# Sensors.net
KiCad netlist of a schematic drawn in Altium Designer
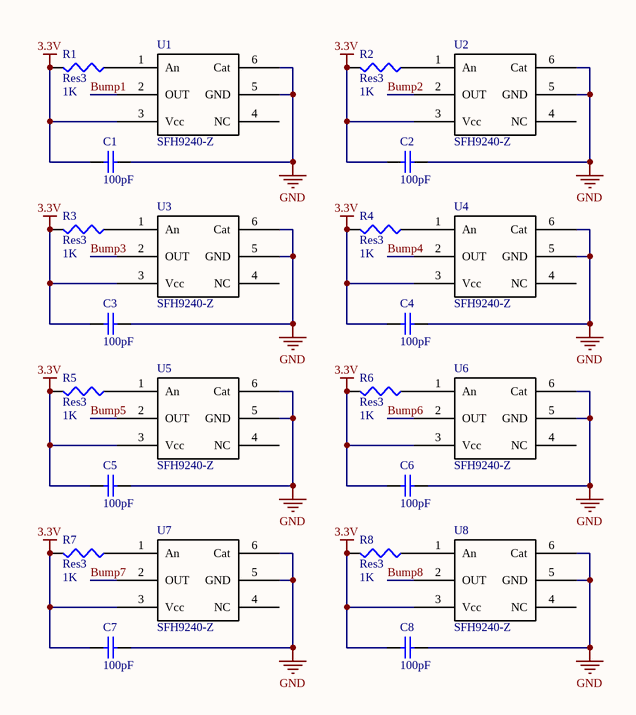
[diagram p0: Sensors.SchDoc]

(export (version "E")
  (design (tool "Eeschema 10.0.6"))
  (components
    (comp (ref "C1")
      (value "100pF")
      (footprint "CAPC1005L")
      (description "Capacitor (Semiconductor SIM Model)")
      (fields (field (name "Comment") "Cap Semi") (field (name "PUBLISHER") "Altium Limited"))
      (libsource (lib "Miscellaneous Devices") (part "Cap Semi"))
    )
    (comp (ref "C2")
      (value "100pF")
      (footprint "CAPC1005L")
      (description "Capacitor (Semiconductor SIM Model)")
      (fields (field (name "Comment") "Cap Semi") (field (name "PUBLISHER") "Altium Limited"))
      (libsource (lib "Miscellaneous Devices") (part "Cap Semi"))
    )
    (comp (ref "C3")
      (value "100pF")
      (footprint "CAPC1005L")
      (description "Capacitor (Semiconductor SIM Model)")
      (fields (field (name "Comment") "Cap Semi") (field (name "PUBLISHER") "Altium Limited"))
      (libsource (lib "Miscellaneous Devices") (part "Cap Semi"))
    )
    (comp (ref "C4")
      (value "100pF")
      (footprint "CAPC1005L")
      (description "Capacitor (Semiconductor SIM Model)")
      (fields (field (name "Comment") "Cap Semi") (field (name "PUBLISHER") "Altium Limited"))
      (libsource (lib "Miscellaneous Devices") (part "Cap Semi"))
    )
    (comp (ref "C5")
      (value "100pF")
      (footprint "CAPC1005L")
      (description "Capacitor (Semiconductor SIM Model)")
      (fields (field (name "Comment") "Cap Semi") (field (name "PUBLISHER") "Altium Limited"))
      (libsource (lib "Miscellaneous Devices") (part "Cap Semi"))
    )
    (comp (ref "C6")
      (value "100pF")
      (footprint "CAPC1005L")
      (description "Capacitor (Semiconductor SIM Model)")
      (fields (field (name "Comment") "Cap Semi") (field (name "PUBLISHER") "Altium Limited"))
      (libsource (lib "Miscellaneous Devices") (part "Cap Semi"))
    )
    (comp (ref "C7")
      (value "100pF")
      (footprint "CAPC1005L")
      (description "Capacitor (Semiconductor SIM Model)")
      (fields (field (name "Comment") "Cap Semi") (field (name "PUBLISHER") "Altium Limited"))
      (libsource (lib "Miscellaneous Devices") (part "Cap Semi"))
    )
    (comp (ref "C8")
      (value "100pF")
      (footprint "CAPC1005L")
      (description "Capacitor (Semiconductor SIM Model)")
      (fields (field (name "Comment") "Cap Semi") (field (name "PUBLISHER") "Altium Limited"))
      (libsource (lib "Miscellaneous Devices") (part "Cap Semi"))
    )
    (comp (ref "R1")
      (value "Res3")
      (footprint "RESC1608L")
      (description "Resistor")
      (fields (field (name "ALTIUM_VALUE") "1K") (field (name "PUBLISHER") "Altium Limited"))
      (libsource (lib "Miscellaneous Devices") (part "Res3"))
    )
    (comp (ref "R2")
      (value "Res3")
      (footprint "RESC1608L")
      (description "Resistor")
      (fields (field (name "ALTIUM_VALUE") "1K") (field (name "PUBLISHER") "Altium Limited"))
      (libsource (lib "Miscellaneous Devices") (part "Res3"))
    )
    (comp (ref "R3")
      (value "Res3")
      (footprint "RESC1608L")
      (description "Resistor")
      (fields (field (name "ALTIUM_VALUE") "1K") (field (name "PUBLISHER") "Altium Limited"))
      (libsource (lib "Miscellaneous Devices") (part "Res3"))
    )
    (comp (ref "R4")
      (value "Res3")
      (footprint "RESC1608L")
      (description "Resistor")
      (fields (field (name "ALTIUM_VALUE") "1K") (field (name "PUBLISHER") "Altium Limited"))
      (libsource (lib "Miscellaneous Devices") (part "Res3"))
    )
    (comp (ref "R5")
      (value "Res3")
      (footprint "RESC1608L")
      (description "Resistor")
      (fields (field (name "ALTIUM_VALUE") "1K") (field (name "PUBLISHER") "Altium Limited"))
      (libsource (lib "Miscellaneous Devices") (part "Res3"))
    )
    (comp (ref "R6")
      (value "Res3")
      (footprint "RESC1608L")
      (description "Resistor")
      (fields (field (name "ALTIUM_VALUE") "1K") (field (name "PUBLISHER") "Altium Limited"))
      (libsource (lib "Miscellaneous Devices") (part "Res3"))
    )
    (comp (ref "R7")
      (value "Res3")
      (footprint "RESC1608L")
      (description "Resistor")
      (fields (field (name "ALTIUM_VALUE") "1K") (field (name "PUBLISHER") "Altium Limited"))
      (libsource (lib "Miscellaneous Devices") (part "Res3"))
    )
    (comp (ref "R8")
      (value "Res3")
      (footprint "RESC1608L")
      (description "Resistor")
      (fields (field (name "ALTIUM_VALUE") "1K") (field (name "PUBLISHER") "Altium Limited"))
      (libsource (lib "Miscellaneous Devices") (part "Res3"))
    )
    (comp (ref "U1") (value "SFH9240-Z") (footprint "SFH9240-Z") (libsource (lib "mrone") (part "SFH9240-Z")))
    (comp (ref "U2") (value "SFH9240-Z") (footprint "SFH9240-Z") (libsource (lib "mrone") (part "SFH9240-Z")))
    (comp (ref "U3") (value "SFH9240-Z") (footprint "SFH9240-Z") (libsource (lib "mrone") (part "SFH9240-Z")))
    (comp (ref "U4") (value "SFH9240-Z") (footprint "SFH9240-Z") (libsource (lib "mrone") (part "SFH9240-Z")))
    (comp (ref "U5") (value "SFH9240-Z") (footprint "SFH9240-Z") (libsource (lib "mrone") (part "SFH9240-Z")))
    (comp (ref "U6") (value "SFH9240-Z") (footprint "SFH9240-Z") (libsource (lib "mrone") (part "SFH9240-Z")))
    (comp (ref "U7") (value "SFH9240-Z") (footprint "SFH9240-Z") (libsource (lib "mrone") (part "SFH9240-Z")))
    (comp (ref "U8") (value "SFH9240-Z") (footprint "SFH9240-Z") (libsource (lib "mrone") (part "SFH9240-Z")))
  )
  (nets
    (net (code "1") (name "/Bump1") (class "Default")
      (node (ref "U1") (pin "2") (pinfunction "OUT_2") (pintype "passive"))
    )
    (net (code "2") (name "/Bump2") (class "Default")
      (node (ref "U2") (pin "2") (pinfunction "OUT_2") (pintype "passive"))
    )
    (net (code "3") (name "/Bump3") (class "Default")
      (node (ref "U3") (pin "2") (pinfunction "OUT_2") (pintype "passive"))
    )
    (net (code "4") (name "/Bump4") (class "Default")
      (node (ref "U4") (pin "2") (pinfunction "OUT_2") (pintype "passive"))
    )
    (net (code "5") (name "/Bump5") (class "Default")
      (node (ref "U5") (pin "2") (pinfunction "OUT_2") (pintype "passive"))
    )
    (net (code "6") (name "/Bump6") (class "Default")
      (node (ref "U6") (pin "2") (pinfunction "OUT_2") (pintype "passive"))
    )
    (net (code "7") (name "/Bump7") (class "Default")
      (node (ref "U7") (pin "2") (pinfunction "OUT_2") (pintype "passive"))
    )
    (net (code "8") (name "/Bump8") (class "Default")
      (node (ref "U8") (pin "2") (pinfunction "OUT_2") (pintype "passive"))
    )
    (net (code "9") (name "3.3V") (class "Default")
      (node (ref "C1") (pin "2") (pinfunction "2_2") (pintype "passive"))
      (node (ref "C2") (pin "2") (pinfunction "2_2") (pintype "passive"))
      (node (ref "C3") (pin "2") (pinfunction "2_2") (pintype "passive"))
      (node (ref "C4") (pin "2") (pinfunction "2_2") (pintype "passive"))
      (node (ref "C5") (pin "2") (pinfunction "2_2") (pintype "passive"))
      (node (ref "C6") (pin "2") (pinfunction "2_2") (pintype "passive"))
      (node (ref "C7") (pin "2") (pinfunction "2_2") (pintype "passive"))
      (node (ref "C8") (pin "2") (pinfunction "2_2") (pintype "passive"))
      (node (ref "R1") (pin "2") (pinfunction "2_2") (pintype "passive"))
      (node (ref "R2") (pin "2") (pinfunction "2_2") (pintype "passive"))
      (node (ref "R3") (pin "2") (pinfunction "2_2") (pintype "passive"))
      (node (ref "R4") (pin "2") (pinfunction "2_2") (pintype "passive"))
      (node (ref "R5") (pin "2") (pinfunction "2_2") (pintype "passive"))
      (node (ref "R6") (pin "2") (pinfunction "2_2") (pintype "passive"))
      (node (ref "R7") (pin "2") (pinfunction "2_2") (pintype "passive"))
      (node (ref "R8") (pin "2") (pinfunction "2_2") (pintype "passive"))
      (node (ref "U1") (pin "3") (pinfunction "Vcc_3") (pintype "passive"))
      (node (ref "U2") (pin "3") (pinfunction "Vcc_3") (pintype "passive"))
      (node (ref "U3") (pin "3") (pinfunction "Vcc_3") (pintype "passive"))
      (node (ref "U4") (pin "3") (pinfunction "Vcc_3") (pintype "passive"))
      (node (ref "U5") (pin "3") (pinfunction "Vcc_3") (pintype "passive"))
      (node (ref "U6") (pin "3") (pinfunction "Vcc_3") (pintype "passive"))
      (node (ref "U7") (pin "3") (pinfunction "Vcc_3") (pintype "passive"))
      (node (ref "U8") (pin "3") (pinfunction "Vcc_3") (pintype "passive"))
    )
    (net (code "10") (name "GND") (class "Default")
      (node (ref "C1") (pin "1") (pinfunction "1_1") (pintype "passive"))
      (node (ref "C2") (pin "1") (pinfunction "1_1") (pintype "passive"))
      (node (ref "C3") (pin "1") (pinfunction "1_1") (pintype "passive"))
      (node (ref "C4") (pin "1") (pinfunction "1_1") (pintype "passive"))
      (node (ref "C5") (pin "1") (pinfunction "1_1") (pintype "passive"))
      (node (ref "C6") (pin "1") (pinfunction "1_1") (pintype "passive"))
      (node (ref "C7") (pin "1") (pinfunction "1_1") (pintype "passive"))
      (node (ref "C8") (pin "1") (pinfunction "1_1") (pintype "passive"))
      (node (ref "U1") (pin "5") (pinfunction "GND_5") (pintype "passive"))
      (node (ref "U1") (pin "6") (pinfunction "Cat_6") (pintype "passive"))
      (node (ref "U2") (pin "5") (pinfunction "GND_5") (pintype "passive"))
      (node (ref "U2") (pin "6") (pinfunction "Cat_6") (pintype "passive"))
      (node (ref "U3") (pin "5") (pinfunction "GND_5") (pintype "passive"))
      (node (ref "U3") (pin "6") (pinfunction "Cat_6") (pintype "passive"))
      (node (ref "U4") (pin "5") (pinfunction "GND_5") (pintype "passive"))
      (node (ref "U4") (pin "6") (pinfunction "Cat_6") (pintype "passive"))
      (node (ref "U5") (pin "5") (pinfunction "GND_5") (pintype "passive"))
      (node (ref "U5") (pin "6") (pinfunction "Cat_6") (pintype "passive"))
      (node (ref "U6") (pin "5") (pinfunction "GND_5") (pintype "passive"))
      (node (ref "U6") (pin "6") (pinfunction "Cat_6") (pintype "passive"))
      (node (ref "U7") (pin "5") (pinfunction "GND_5") (pintype "passive"))
      (node (ref "U7") (pin "6") (pinfunction "Cat_6") (pintype "passive"))
      (node (ref "U8") (pin "5") (pinfunction "GND_5") (pintype "passive"))
      (node (ref "U8") (pin "6") (pinfunction "Cat_6") (pintype "passive"))
    )
    (net (code "11") (name "Net-(U1-An)") (class "Default")
      (node (ref "R1") (pin "1") (pinfunction "1_1") (pintype "passive"))
      (node (ref "U1") (pin "1") (pinfunction "An_1") (pintype "passive"))
    )
    (net (code "12") (name "Net-(U2-An)") (class "Default")
      (node (ref "R2") (pin "1") (pinfunction "1_1") (pintype "passive"))
      (node (ref "U2") (pin "1") (pinfunction "An_1") (pintype "passive"))
    )
    (net (code "13") (name "Net-(U3-An)") (class "Default")
      (node (ref "R3") (pin "1") (pinfunction "1_1") (pintype "passive"))
      (node (ref "U3") (pin "1") (pinfunction "An_1") (pintype "passive"))
    )
    (net (code "14") (name "Net-(U4-An)") (class "Default")
      (node (ref "R4") (pin "1") (pinfunction "1_1") (pintype "passive"))
      (node (ref "U4") (pin "1") (pinfunction "An_1") (pintype "passive"))
    )
    (net (code "15") (name "Net-(U5-An)") (class "Default")
      (node (ref "R5") (pin "1") (pinfunction "1_1") (pintype "passive"))
      (node (ref "U5") (pin "1") (pinfunction "An_1") (pintype "passive"))
    )
    (net (code "16") (name "Net-(U6-An)") (class "Default")
      (node (ref "R6") (pin "1") (pinfunction "1_1") (pintype "passive"))
      (node (ref "U6") (pin "1") (pinfunction "An_1") (pintype "passive"))
    )
    (net (code "17") (name "Net-(U7-An)") (class "Default")
      (node (ref "R7") (pin "1") (pinfunction "1_1") (pintype "passive"))
      (node (ref "U7") (pin "1") (pinfunction "An_1") (pintype "passive"))
    )
    (net (code "18") (name "Net-(U8-An)") (class "Default")
      (node (ref "R8") (pin "1") (pinfunction "1_1") (pintype "passive"))
      (node (ref "U8") (pin "1") (pinfunction "An_1") (pintype "passive"))
    )
    (net (code "19") (name "unconnected-(U1-NC-Pad4)") (class "Default")
      (node (ref "U1") (pin "4") (pinfunction "NC_4") (pintype "passive"))
    )
    (net (code "20") (name "unconnected-(U2-NC-Pad4)") (class "Default")
      (node (ref "U2") (pin "4") (pinfunction "NC_4") (pintype "passive"))
    )
    (net (code "21") (name "unconnected-(U3-NC-Pad4)") (class "Default")
      (node (ref "U3") (pin "4") (pinfunction "NC_4") (pintype "passive"))
    )
    (net (code "22") (name "unconnected-(U4-NC-Pad4)") (class "Default")
      (node (ref "U4") (pin "4") (pinfunction "NC_4") (pintype "passive"))
    )
    (net (code "23") (name "unconnected-(U5-NC-Pad4)") (class "Default")
      (node (ref "U5") (pin "4") (pinfunction "NC_4") (pintype "passive"))
    )
    (net (code "24") (name "unconnected-(U6-NC-Pad4)") (class "Default")
      (node (ref "U6") (pin "4") (pinfunction "NC_4") (pintype "passive"))
    )
    (net (code "25") (name "unconnected-(U7-NC-Pad4)") (class "Default")
      (node (ref "U7") (pin "4") (pinfunction "NC_4") (pintype "passive"))
    )
    (net (code "26") (name "unconnected-(U8-NC-Pad4)") (class "Default")
      (node (ref "U8") (pin "4") (pinfunction "NC_4") (pintype "passive"))
    )
  )
)
